# PCB_Design_Project.net
KiCad netlist of a schematic drawn in EasyEDA Pro
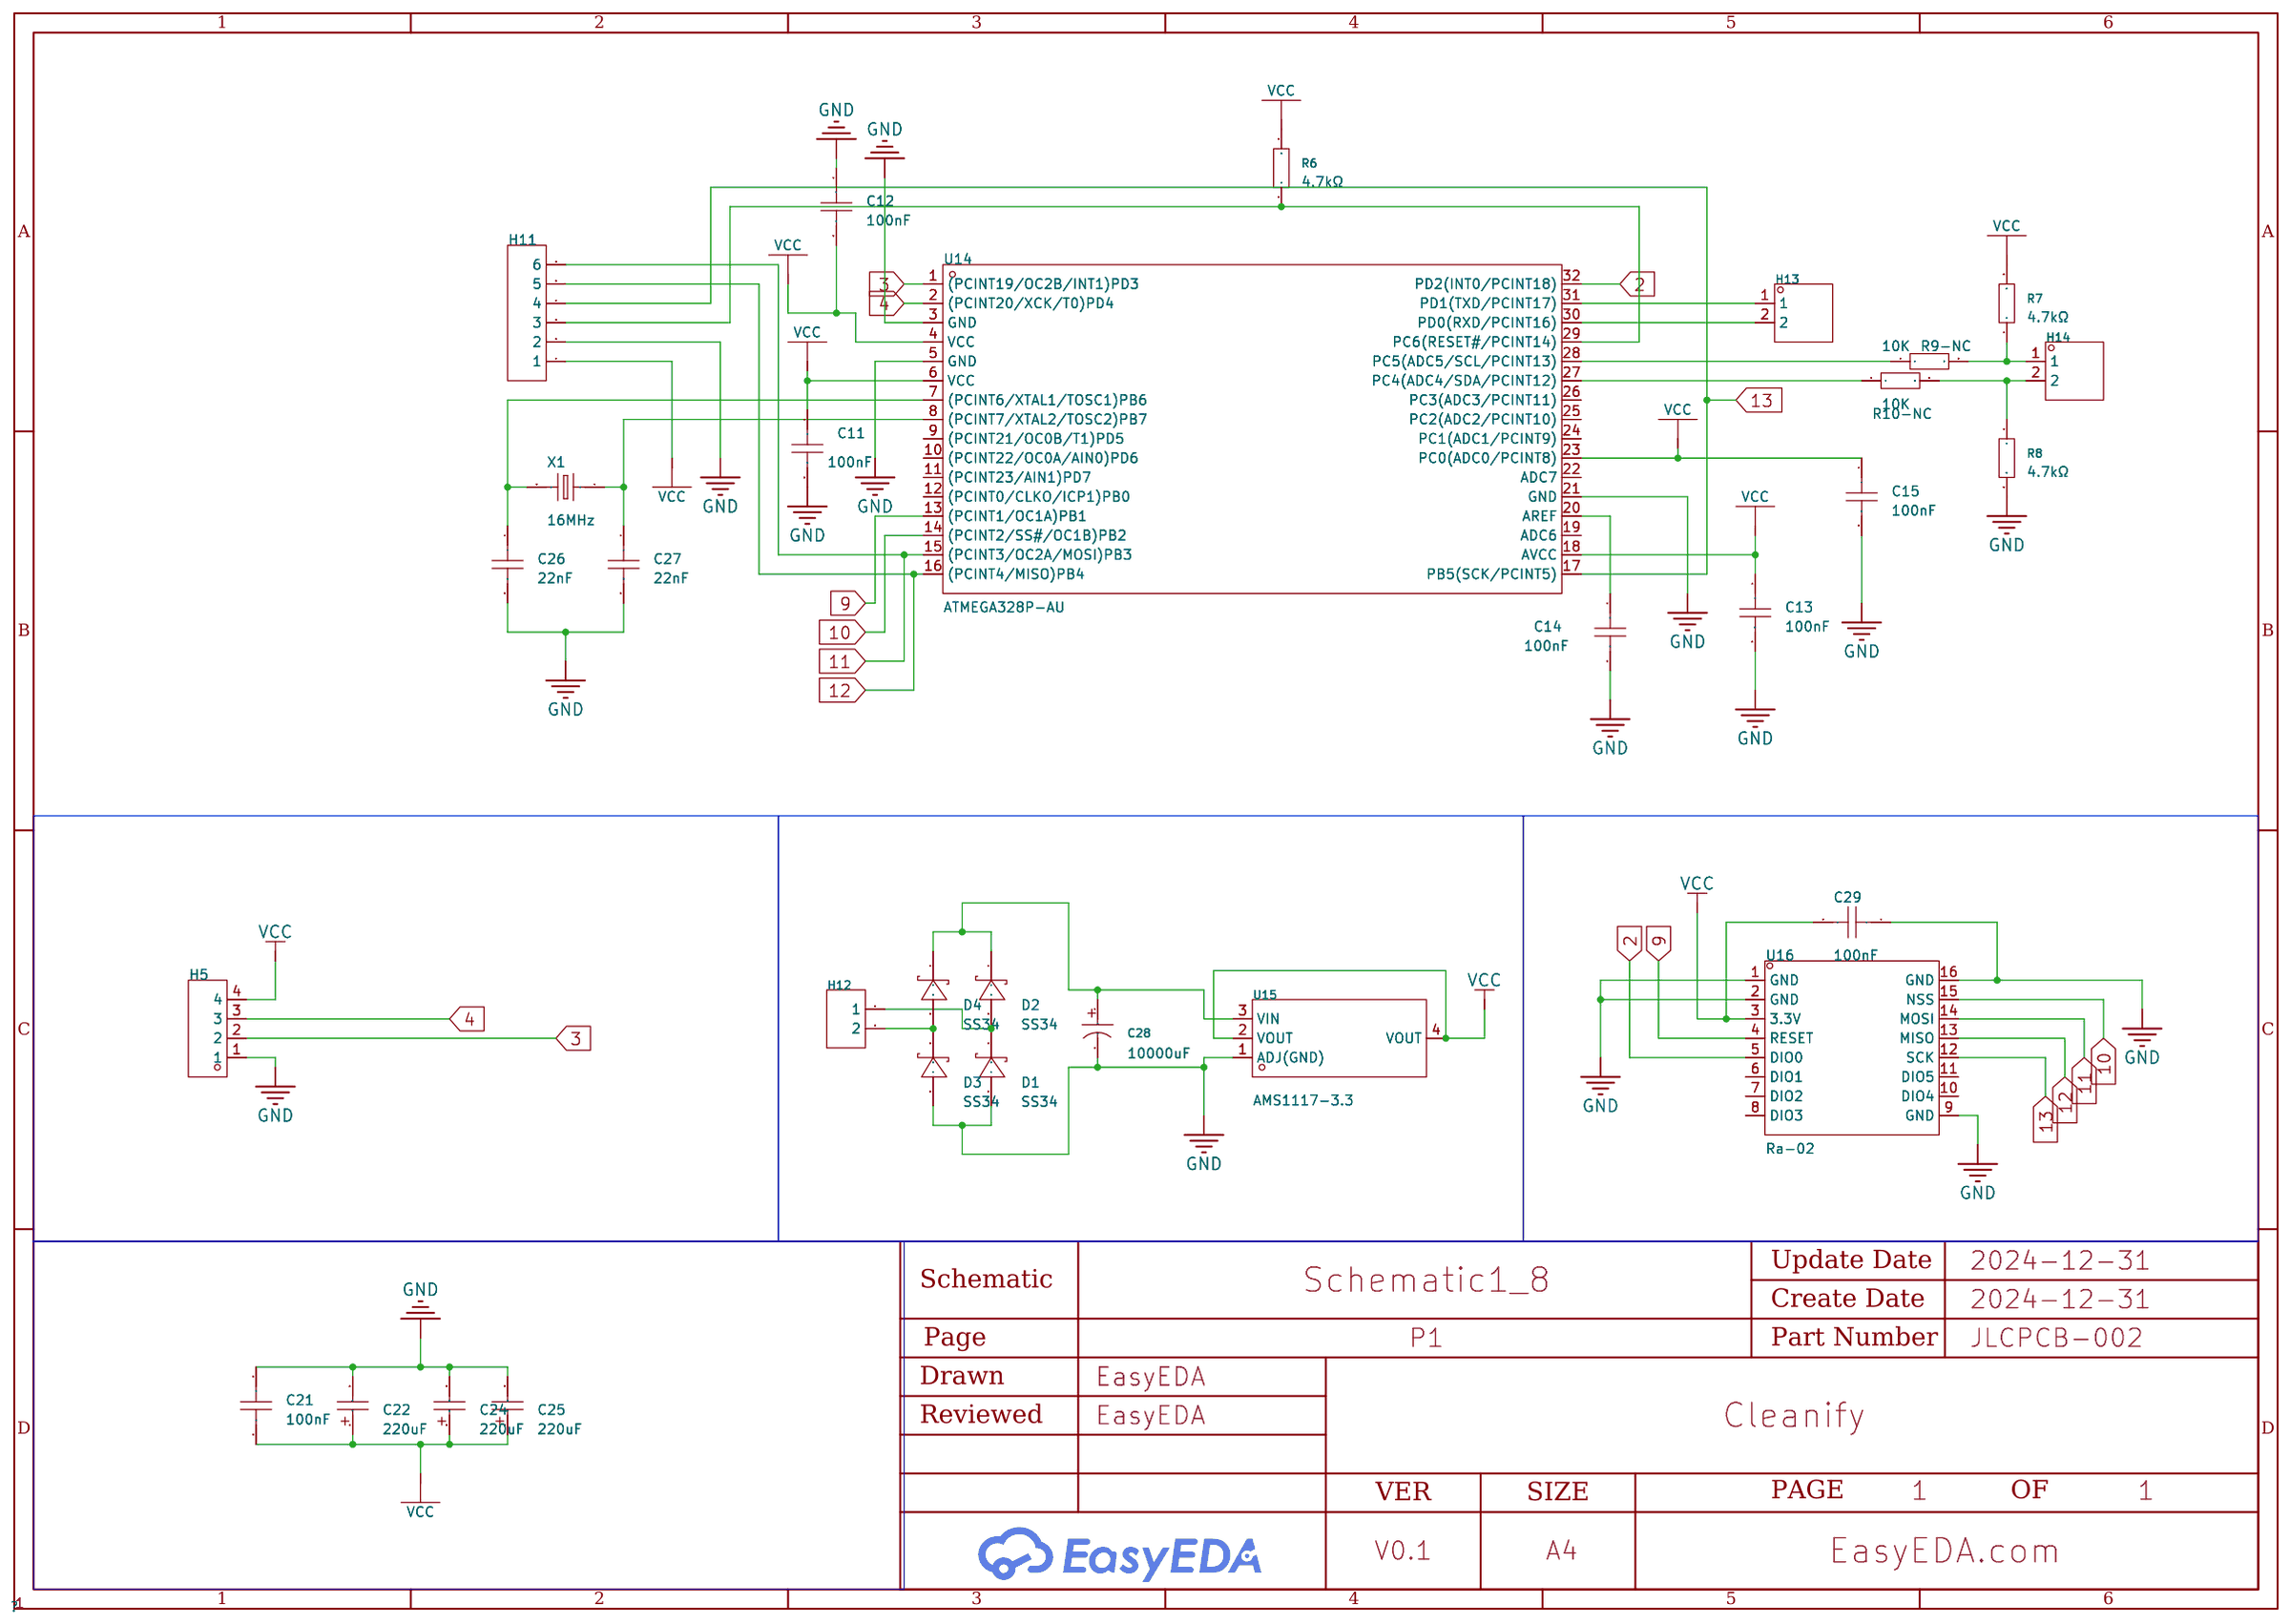
[diagram p0: schematic sheet]

(export (version "E")
  (design (tool "Eeschema 10.0.6"))
  (components
    (comp (ref "C11")
      (value "100nF")
      (footprint "easyedapro:C0805")
      (libsource (lib "easyedapro") (part "CAP"))
    )
    (comp (ref "C12")
      (value "100nF")
      (footprint "easyedapro:C0805")
      (libsource (lib "easyedapro") (part "CAP"))
    )
    (comp (ref "C13")
      (value "100nF")
      (footprint "easyedapro:C0805")
      (libsource (lib "easyedapro") (part "CAP"))
    )
    (comp (ref "C14")
      (value "100nF")
      (footprint "easyedapro:C0805")
      (libsource (lib "easyedapro") (part "CAP"))
    )
    (comp (ref "C15")
      (value "100nF")
      (footprint "easyedapro:C0805")
      (libsource (lib "easyedapro") (part "CAP"))
    )
    (comp (ref "C21")
      (value "100nF")
      (footprint "easyedapro:C0805")
      (libsource (lib "easyedapro") (part "CAP"))
    )
    (comp (ref "C22")
      (value "220uF")
      (footprint "easyedapro:CAP-SMD_L3.5-W2.8-R-RD")
      (fields (field (name "Manufacturer Part") "TAJB227M004RNJ") (field (name "Manufacturer") "Kyocera AVX"))
      (libsource (lib "easyedapro") (part "TAJB227M004RNJ"))
    )
    (comp (ref "C24")
      (value "220uF")
      (footprint "easyedapro:CAP-SMD_L3.5-W2.8-R-RD")
      (fields (field (name "Manufacturer Part") "TAJB227M004RNJ") (field (name "Manufacturer") "Kyocera AVX"))
      (libsource (lib "easyedapro") (part "TAJB227M004RNJ"))
    )
    (comp (ref "C25")
      (value "220uF")
      (footprint "easyedapro:CAP-SMD_L3.5-W2.8-R-RD")
      (fields (field (name "Manufacturer Part") "TAJB227M004RNJ") (field (name "Manufacturer") "Kyocera AVX"))
      (libsource (lib "easyedapro") (part "TAJB227M004RNJ"))
    )
    (comp (ref "C26")
      (value "22nF")
      (footprint "easyedapro:C0805")
      (libsource (lib "easyedapro") (part "CAP"))
    )
    (comp (ref "C27")
      (value "22nF")
      (footprint "easyedapro:C0805")
      (libsource (lib "easyedapro") (part "CAP"))
    )
    (comp (ref "C28")
      (value "10000uF")
      (footprint "easyedapro:CAP-TH_BD22.0-P10.00-D1.4-FD")
      (fields
        (field (name "Manufacturer Part") "KM109M016N30RR0VH2FP0")
        (field (name "Manufacturer") "CX(承兴)")
      )
      (libsource (lib "easyedapro") (part "10000uF 16V 22*30"))
    )
    (comp (ref "C29")
      (value "100nF")
      (footprint "easyedapro:C0805")
      (libsource (lib "easyedapro") (part "CAP"))
    )
    (comp (ref "D1")
      (value "SS34")
      (footprint "easyedapro:SMA_L4.3-W2.6-LS5.2-RD")
      (fields (field (name "Manufacturer") "MDD(辰达半导体)"))
      (libsource (lib "easyedapro") (part "SS34_C8678"))
    )
    (comp (ref "D2")
      (value "SS34")
      (footprint "easyedapro:SMA_L4.3-W2.6-LS5.2-RD")
      (fields (field (name "Manufacturer") "MDD(辰达半导体)"))
      (libsource (lib "easyedapro") (part "SS34_C8678"))
    )
    (comp (ref "D3")
      (value "SS34")
      (footprint "easyedapro:SMA_L4.3-W2.6-LS5.2-RD")
      (fields (field (name "Manufacturer") "MDD(辰达半导体)"))
      (libsource (lib "easyedapro") (part "SS34_C8678"))
    )
    (comp (ref "D4")
      (value "SS34")
      (footprint "easyedapro:SMA_L4.3-W2.6-LS5.2-RD")
      (fields (field (name "Manufacturer") "MDD(辰达半导体)"))
      (libsource (lib "easyedapro") (part "SS34_C8678"))
    )
    (comp (ref "H5")
      (value "~")
      (footprint "easyedapro:HDR-TH_4P-P2.54-V-M")
      (libsource (lib "easyedapro") (part "PZ254V-11-04P"))
    )
    (comp (ref "H11")
      (value "~")
      (footprint "easyedapro:HDR-TH_6P-P2.54-V-M-1")
      (libsource (lib "easyedapro") (part "Header-Male-2.54_1x6"))
    )
    (comp (ref "H12")
      (value "~")
      (footprint "easyedapro:HDR-TH_2P-P2.54-V-F")
      (libsource (lib "easyedapro") (part "Header-Female-2.54_1x2"))
    )
    (comp (ref "H13")
      (value "~")
      (footprint "easyedapro:HDR-TH_2P-P2.54-V-M-1")
      (libsource (lib "easyedapro") (part "210S-1*2P L=11.6MMGold-plated black"))
    )
    (comp (ref "H14")
      (value "~")
      (footprint "easyedapro:HDR-TH_2P-P2.54-V-M-1")
      (libsource (lib "easyedapro") (part "210S-1*2P L=11.6MMGold-plated black"))
    )
    (comp (ref "R6")
      (value "4.7kΩ")
      (footprint "easyedapro:R0805")
      (fields (field (name "Manufacturer Part") "RMC08054.7K1%N") (field (name "Manufacturer") "Tyohm(幸亚电阻)"))
      (libsource (lib "easyedapro") (part "RMC08054.7K1%N"))
    )
    (comp (ref "R7")
      (value "4.7kΩ")
      (footprint "easyedapro:R0805")
      (fields (field (name "Manufacturer Part") "RMC08054.7K1%N") (field (name "Manufacturer") "Tyohm(幸亚电阻)"))
      (libsource (lib "easyedapro") (part "RMC08054.7K1%N"))
    )
    (comp (ref "R8")
      (value "4.7kΩ")
      (footprint "easyedapro:R0805")
      (fields (field (name "Manufacturer Part") "RMC08054.7K1%N") (field (name "Manufacturer") "Tyohm(幸亚电阻)"))
      (libsource (lib "easyedapro") (part "RMC08054.7K1%N"))
    )
    (comp (ref "R9-NC")
      (value "10K")
      (footprint "easyedapro:R0201")
      (libsource (lib "easyedapro") (part "Res"))
    )
    (comp (ref "R10-NC")
      (value "10K")
      (footprint "easyedapro:R0201")
      (libsource (lib "easyedapro") (part "Res"))
    )
    (comp (ref "U14")
      (value "ATMEGA328P-AU")
      (footprint "easyedapro:TQFP-32_L7.0-W7.0-P0.80-LS9.0-BL")
      (fields (field (name "Manufacturer") "MICROCHIP(美国微芯)"))
      (libsource (lib "easyedapro") (part "ATMEGA328P-AU"))
    )
    (comp (ref "U15")
      (value "AMS1117-3.3")
      (footprint "easyedapro:SOT-223-3_L6.5-W3.4-P2.30-LS7.0-BR")
      (fields (field (name "Manufacturer") "YONGYUTAI(永裕泰)"))
      (libsource (lib "easyedapro") (part "AMS1117-3.3_C2891839"))
    )
    (comp (ref "U16")
      (value "Ra-02")
      (footprint "easyedapro:WIRELM-SMD_RA-02-BL")
      (fields (field (name "Manufacturer") "Ai-Thinker(安信可)"))
      (libsource (lib "easyedapro") (part "RA-02"))
    )
    (comp (ref "X1")
      (value "16MHz")
      (footprint "easyedapro:HC-49US_L11.5-W4.5-P4.88")
      (fields
        (field (name "Manufacturer Part") "XIHCELNANF-16MHZ")
        (field (name "Manufacturer") "TAITIEN(泰艺电子)")
      )
      (libsource (lib "easyedapro") (part "XIHCELNANF-16MHZ"))
    )
  )
  (nets
    (net (code "1") (name "2") (class "Default")
      (node (ref "U14") (pin "32") (pinfunction "PD2(INT0/PCINT18)_32") (pintype "unspecified"))
      (node (ref "U16") (pin "5") (pinfunction "DIO0_5") (pintype "unspecified"))
    )
    (net (code "2") (name "3") (class "Default")
      (node (ref "H5") (pin "2") (pinfunction "2_2") (pintype "unspecified"))
      (node (ref "U14") (pin "1") (pinfunction "(PCINT19/OC2B/INT1)PD3_1") (pintype "unspecified"))
    )
    (net (code "3") (name "4") (class "Default")
      (node (ref "H5") (pin "3") (pinfunction "3_3") (pintype "unspecified"))
      (node (ref "U14") (pin "2") (pinfunction "(PCINT20/XCK/T0)PD4_2") (pintype "unspecified"))
    )
    (net (code "4") (name "9") (class "Default")
      (node (ref "U14") (pin "13") (pinfunction "(PCINT1/OC1A)PB1_13") (pintype "unspecified"))
      (node (ref "U16") (pin "4") (pinfunction "RESET_4") (pintype "unspecified"))
    )
    (net (code "5") (name "10") (class "Default")
      (node (ref "U14") (pin "14") (pinfunction "(PCINT2/SS#/OC1B)PB2_14") (pintype "unspecified"))
      (node (ref "U16") (pin "15") (pinfunction "NSS_15") (pintype "unspecified"))
    )
    (net (code "6") (name "11") (class "Default")
      (node (ref "H11") (pin "6") (pinfunction "6_6") (pintype "input"))
      (node (ref "U14") (pin "15") (pinfunction "(PCINT3/OC2A/MOSI)PB3_15") (pintype "unspecified"))
      (node (ref "U16") (pin "14") (pinfunction "MOSI_14") (pintype "unspecified"))
    )
    (net (code "7") (name "12") (class "Default")
      (node (ref "H11") (pin "5") (pinfunction "5_5") (pintype "input"))
      (node (ref "U14") (pin "16") (pinfunction "(PCINT4/MISO)PB4_16") (pintype "unspecified"))
      (node (ref "U16") (pin "13") (pinfunction "MISO_13") (pintype "unspecified"))
    )
    (net (code "8") (name "13") (class "Default")
      (node (ref "H11") (pin "4") (pinfunction "4_4") (pintype "input"))
      (node (ref "U14") (pin "17") (pinfunction "PB5(SCK/PCINT5)_17") (pintype "unspecified"))
      (node (ref "U16") (pin "12") (pinfunction "SCK_12") (pintype "unspecified"))
    )
    (net (code "9") (name "GND") (class "Default")
      (node (ref "C11") (pin "2") (pinfunction "2_2") (pintype "input"))
      (node (ref "C12") (pin "1") (pinfunction "1_1") (pintype "input"))
      (node (ref "C13") (pin "2") (pinfunction "2_2") (pintype "input"))
      (node (ref "C14") (pin "2") (pinfunction "2_2") (pintype "input"))
      (node (ref "C15") (pin "2") (pinfunction "2_2") (pintype "input"))
      (node (ref "C21") (pin "1") (pinfunction "1_1") (pintype "input"))
      (node (ref "C22") (pin "2") (pinfunction "2_2") (pintype "input"))
      (node (ref "C24") (pin "2") (pinfunction "2_2") (pintype "input"))
      (node (ref "C25") (pin "2") (pinfunction "2_2") (pintype "input"))
      (node (ref "C26") (pin "2") (pinfunction "2_2") (pintype "input"))
      (node (ref "C27") (pin "2") (pinfunction "2_2") (pintype "input"))
      (node (ref "C28") (pin "2") (pinfunction "2_2") (pintype "input"))
      (node (ref "C29") (pin "1") (pinfunction "1_1") (pintype "input"))
      (node (ref "D1") (pin "2") (pinfunction "A_2") (pintype "unspecified"))
      (node (ref "D3") (pin "2") (pinfunction "A_2") (pintype "unspecified"))
      (node (ref "H11") (pin "2") (pinfunction "2_2") (pintype "input"))
      (node (ref "H5") (pin "1") (pinfunction "1_1") (pintype "unspecified"))
      (node (ref "R8") (pin "2") (pinfunction "2_2") (pintype "input"))
      (node (ref "U14") (pin "21") (pinfunction "GND_21") (pintype "unspecified"))
      (node (ref "U14") (pin "3") (pinfunction "GND_3") (pintype "unspecified"))
      (node (ref "U14") (pin "5") (pinfunction "GND_5") (pintype "unspecified"))
      (node (ref "U15") (pin "1") (pinfunction "ADJ(GND)_1") (pintype "input"))
      (node (ref "U16") (pin "1") (pinfunction "GND_1") (pintype "unspecified"))
      (node (ref "U16") (pin "16") (pinfunction "GND_16") (pintype "unspecified"))
      (node (ref "U16") (pin "2") (pinfunction "GND_2") (pintype "unspecified"))
      (node (ref "U16") (pin "9") (pinfunction "GND_9") (pintype "unspecified"))
    )
    (net (code "10") (name "Net-(D1-K)") (class "Default")
      (node (ref "D1") (pin "1") (pinfunction "K_1") (pintype "unspecified"))
      (node (ref "D2") (pin "2") (pinfunction "A_2") (pintype "unspecified"))
      (node (ref "H12") (pin "1") (pinfunction "1_1") (pintype "input"))
    )
    (net (code "11") (name "Net-(D2-K)") (class "Default")
      (node (ref "C28") (pin "1") (pinfunction "1_1") (pintype "input"))
      (node (ref "D2") (pin "1") (pinfunction "K_1") (pintype "unspecified"))
      (node (ref "D4") (pin "1") (pinfunction "K_1") (pintype "unspecified"))
      (node (ref "U15") (pin "3") (pinfunction "VIN_3") (pintype "input"))
    )
    (net (code "12") (name "Net-(D3-K)") (class "Default")
      (node (ref "D3") (pin "1") (pinfunction "K_1") (pintype "unspecified"))
      (node (ref "D4") (pin "2") (pinfunction "A_2") (pintype "unspecified"))
      (node (ref "H12") (pin "2") (pinfunction "2_2") (pintype "input"))
    )
    (net (code "13") (name "Net-(H14-Pad1)") (class "Default")
      (node (ref "H14") (pin "1") (pinfunction "1_1") (pintype "input"))
      (node (ref "R7") (pin "1") (pinfunction "1_1") (pintype "input"))
      (node (ref "R9-NC") (pin "2") (pinfunction "2_2") (pintype "input"))
    )
    (net (code "14") (name "Net-(H14-Pad2)") (class "Default")
      (node (ref "H14") (pin "2") (pinfunction "2_2") (pintype "input"))
      (node (ref "R10-NC") (pin "2") (pinfunction "2_2") (pintype "input"))
      (node (ref "R8") (pin "1") (pinfunction "1_1") (pintype "input"))
    )
    (net (code "15") (name "Net-(U14-(PCINT6{slash}XTAL1{slash}TOSC1)PB6)") (class "Default")
      (node (ref "C26") (pin "1") (pinfunction "1_1") (pintype "input"))
      (node (ref "U14") (pin "7") (pinfunction "(PCINT6/XTAL1/TOSC1)PB6_7") (pintype "unspecified"))
      (node (ref "X1") (pin "2") (pinfunction "2_2") (pintype "unspecified"))
    )
    (net (code "16") (name "Net-(U14-(PCINT7{slash}XTAL2{slash}TOSC2)PB7)") (class "Default")
      (node (ref "C27") (pin "1") (pinfunction "1_1") (pintype "input"))
      (node (ref "U14") (pin "8") (pinfunction "(PCINT7/XTAL2/TOSC2)PB7_8") (pintype "unspecified"))
      (node (ref "X1") (pin "1") (pinfunction "1_1") (pintype "unspecified"))
    )
    (net (code "17") (name "Net-(U14-AREF)") (class "Default")
      (node (ref "C14") (pin "1") (pinfunction "1_1") (pintype "input"))
      (node (ref "U14") (pin "20") (pinfunction "AREF_20") (pintype "unspecified"))
    )
    (net (code "18") (name "Net-(U14-PC4(ADC4{slash}SDA{slash}PCINT12))") (class "Default")
      (node (ref "R10-NC") (pin "1") (pinfunction "1_1") (pintype "input"))
      (node (ref "U14") (pin "27") (pinfunction "PC4(ADC4/SDA/PCINT12)_27") (pintype "unspecified"))
    )
    (net (code "19") (name "Net-(U14-PC5(ADC5{slash}SCL{slash}PCINT13))") (class "Default")
      (node (ref "R9-NC") (pin "1") (pinfunction "1_1") (pintype "input"))
      (node (ref "U14") (pin "28") (pinfunction "PC5(ADC5/SCL/PCINT13)_28") (pintype "unspecified"))
    )
    (net (code "20") (name "Net-(U14-PC6(RESET#{slash}PCINT14))") (class "Default")
      (node (ref "H11") (pin "3") (pinfunction "3_3") (pintype "input"))
      (node (ref "R6") (pin "1") (pinfunction "1_1") (pintype "input"))
      (node (ref "U14") (pin "29") (pinfunction "PC6(RESET#/PCINT14)_29") (pintype "unspecified"))
    )
    (net (code "21") (name "Net-(U14-PD0(RXD{slash}PCINT16))") (class "Default")
      (node (ref "H13") (pin "2") (pinfunction "2_2") (pintype "input"))
      (node (ref "U14") (pin "30") (pinfunction "PD0(RXD/PCINT16)_30") (pintype "unspecified"))
    )
    (net (code "22") (name "Net-(U14-PD1(TXD{slash}PCINT17))") (class "Default")
      (node (ref "H13") (pin "1") (pinfunction "1_1") (pintype "input"))
      (node (ref "U14") (pin "31") (pinfunction "PD1(TXD/PCINT17)_31") (pintype "unspecified"))
    )
    (net (code "23") (name "VCC") (class "Default")
      (node (ref "C11") (pin "1") (pinfunction "1_1") (pintype "input"))
      (node (ref "C12") (pin "2") (pinfunction "2_2") (pintype "input"))
      (node (ref "C13") (pin "1") (pinfunction "1_1") (pintype "input"))
      (node (ref "C15") (pin "1") (pinfunction "1_1") (pintype "input"))
      (node (ref "C21") (pin "2") (pinfunction "2_2") (pintype "input"))
      (node (ref "C22") (pin "1") (pinfunction "1_1") (pintype "input"))
      (node (ref "C24") (pin "1") (pinfunction "1_1") (pintype "input"))
      (node (ref "C25") (pin "1") (pinfunction "1_1") (pintype "input"))
      (node (ref "C29") (pin "2") (pinfunction "2_2") (pintype "input"))
      (node (ref "H11") (pin "1") (pinfunction "1_1") (pintype "input"))
      (node (ref "H5") (pin "4") (pinfunction "4_4") (pintype "unspecified"))
      (node (ref "R6") (pin "2") (pinfunction "2_2") (pintype "input"))
      (node (ref "R7") (pin "2") (pinfunction "2_2") (pintype "input"))
      (node (ref "U14") (pin "18") (pinfunction "AVCC_18") (pintype "unspecified"))
      (node (ref "U14") (pin "23") (pinfunction "PC0(ADC0/PCINT8)_23") (pintype "unspecified"))
      (node (ref "U14") (pin "4") (pinfunction "VCC_4") (pintype "unspecified"))
      (node (ref "U14") (pin "6") (pinfunction "VCC_6") (pintype "unspecified"))
      (node (ref "U15") (pin "2") (pinfunction "VOUT_2") (pintype "input"))
      (node (ref "U15") (pin "4") (pinfunction "VOUT_4") (pintype "input"))
      (node (ref "U16") (pin "3") (pinfunction "3.3V_3") (pintype "unspecified"))
    )
    (net (code "24") (name "unconnected-(U14-(PCINT0{slash}CLKO{slash}ICP1)PB0-Pad12)") (class "Default")
      (node (ref "U14") (pin "12") (pinfunction "(PCINT0/CLKO/ICP1)PB0_12") (pintype "unspecified"))
    )
    (net (code "25") (name "unconnected-(U14-(PCINT21{slash}OC0B{slash}T1)PD5-Pad9)") (class "Default")
      (node (ref "U14") (pin "9") (pinfunction "(PCINT21/OC0B/T1)PD5_9") (pintype "unspecified"))
    )
    (net (code "26") (name "unconnected-(U14-(PCINT22{slash}OC0A{slash}AIN0)PD6-Pad10)") (class "Default")
      (node (ref "U14") (pin "10") (pinfunction "(PCINT22/OC0A/AIN0)PD6_10") (pintype "unspecified"))
    )
    (net (code "27") (name "unconnected-(U14-(PCINT23{slash}AIN1)PD7-Pad11)") (class "Default")
      (node (ref "U14") (pin "11") (pinfunction "(PCINT23/AIN1)PD7_11") (pintype "unspecified"))
    )
    (net (code "28") (name "unconnected-(U14-ADC6-Pad19)") (class "Default")
      (node (ref "U14") (pin "19") (pinfunction "ADC6_19") (pintype "unspecified"))
    )
    (net (code "29") (name "unconnected-(U14-ADC7-Pad22)") (class "Default")
      (node (ref "U14") (pin "22") (pinfunction "ADC7_22") (pintype "unspecified"))
    )
    (net (code "30") (name "unconnected-(U14-PC1(ADC1{slash}PCINT9)-Pad24)") (class "Default")
      (node (ref "U14") (pin "24") (pinfunction "PC1(ADC1/PCINT9)_24") (pintype "unspecified"))
    )
    (net (code "31") (name "unconnected-(U14-PC2(ADC2{slash}PCINT10)-Pad25)") (class "Default")
      (node (ref "U14") (pin "25") (pinfunction "PC2(ADC2/PCINT10)_25") (pintype "unspecified"))
    )
    (net (code "32") (name "unconnected-(U14-PC3(ADC3{slash}PCINT11)-Pad26)") (class "Default")
      (node (ref "U14") (pin "26") (pinfunction "PC3(ADC3/PCINT11)_26") (pintype "unspecified"))
    )
    (net (code "33") (name "unconnected-(U16-DIO1-Pad6)") (class "Default")
      (node (ref "U16") (pin "6") (pinfunction "DIO1_6") (pintype "unspecified"))
    )
    (net (code "34") (name "unconnected-(U16-DIO2-Pad7)") (class "Default")
      (node (ref "U16") (pin "7") (pinfunction "DIO2_7") (pintype "unspecified"))
    )
    (net (code "35") (name "unconnected-(U16-DIO3-Pad8)") (class "Default")
      (node (ref "U16") (pin "8") (pinfunction "DIO3_8") (pintype "unspecified"))
    )
    (net (code "36") (name "unconnected-(U16-DIO4-Pad10)") (class "Default")
      (node (ref "U16") (pin "10") (pinfunction "DIO4_10") (pintype "unspecified"))
    )
    (net (code "37") (name "unconnected-(U16-DIO5-Pad11)") (class "Default")
      (node (ref "U16") (pin "11") (pinfunction "DIO5_11") (pintype "unspecified"))
    )
  )
)
